# NOR.net
KiCad netlist of a schematic drawn in Altium Designer
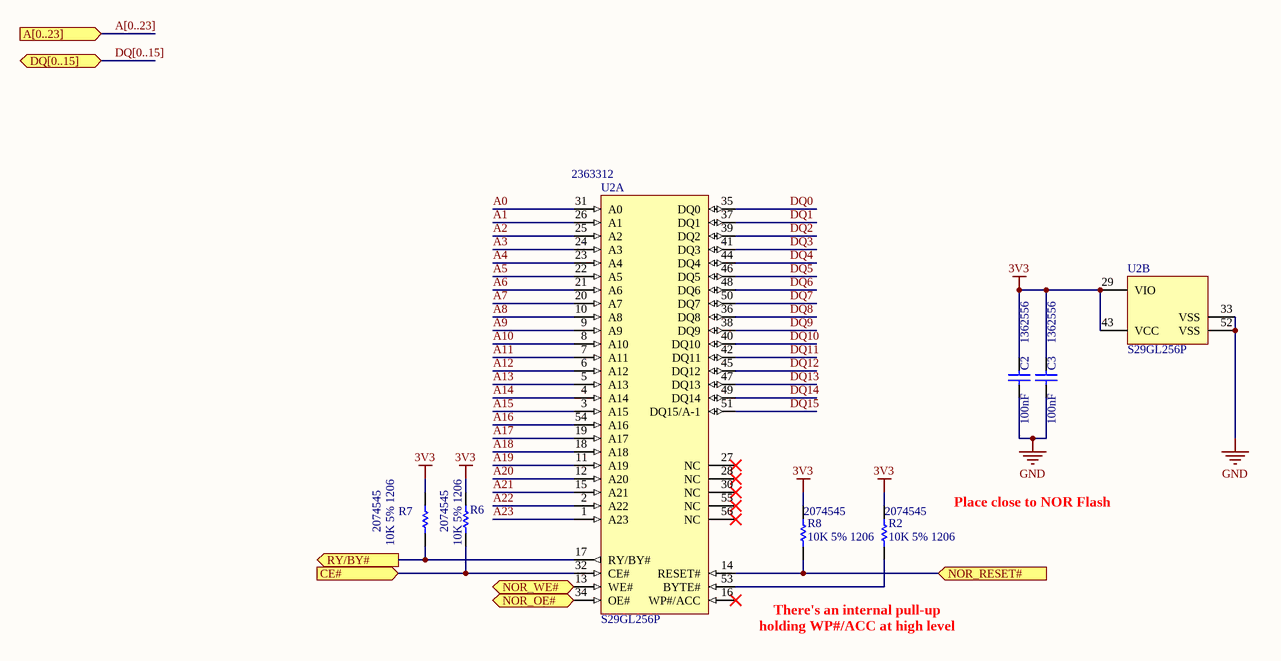
[diagram p0: NOR.SchDoc]

(export (version "E")
  (design (tool "Eeschema 10.0.6"))
  (components
    (comp (ref "C2")
      (value "100nF")
      (footprint "CAPC0603(1608)100_N")
      (description "CAP 100nF 50V ±10% 0603 (1608 Metric) Thickness 1mm SMD")
      (fields (field (name "TOLERANCE") "±10%") (field (name "SUPPLIER PART NUMBER 1") "1362556"))
      (libsource (lib "Altium Content Vault") (part "CMP-1035-02592-1"))
    )
    (comp (ref "C3")
      (value "100nF")
      (footprint "CAPC0603(1608)100_N")
      (description "CAP 100nF 50V ±10% 0603 (1608 Metric) Thickness 1mm SMD")
      (fields (field (name "TOLERANCE") "±10%") (field (name "SUPPLIER PART NUMBER 1") "1362556"))
      (libsource (lib "Altium Content Vault") (part "CMP-1035-02592-1"))
    )
    (comp (ref "R2")
      (value "10K 5% 1206")
      (footprint "RESC1206(3216)_M")
      (description "10K 0.25W 5% 1206 (3216 Metric)  SMD")
      (fields
        (field (name "POWER") "0.25 W")
        (field (name "TOLERANCE") "5 %")
        (field (name "SUPPLIER PART NUMBER 1") "2074545")
      )
      (libsource (lib "Altium Content Vault") (part "CMP-1014-00098-1"))
    )
    (comp (ref "R6")
      (value "10K 5% 1206")
      (footprint "RESC1206(3216)_M")
      (description "10K 0.25W 5% 1206 (3216 Metric)  SMD")
      (fields
        (field (name "POWER") "0.25 W")
        (field (name "TOLERANCE") "5 %")
        (field (name "SUPPLIER PART NUMBER 1") "2074545")
      )
      (libsource (lib "Altium Content Vault") (part "CMP-1014-00098-1"))
    )
    (comp (ref "R7")
      (value "10K 5% 1206")
      (footprint "RESC1206(3216)_M")
      (description "10K 0.25W 5% 1206 (3216 Metric)  SMD")
      (fields
        (field (name "POWER") "0.25 W")
        (field (name "TOLERANCE") "5 %")
        (field (name "SUPPLIER PART NUMBER 1") "2074545")
      )
      (libsource (lib "Altium Content Vault") (part "CMP-1014-00098-1"))
    )
    (comp (ref "R8")
      (value "10K 5% 1206")
      (footprint "RESC1206(3216)_M")
      (description "10K 0.25W 5% 1206 (3216 Metric)  SMD")
      (fields
        (field (name "POWER") "0.25 W")
        (field (name "TOLERANCE") "5 %")
        (field (name "SUPPLIER PART NUMBER 1") "2074545")
      )
      (libsource (lib "Altium Content Vault") (part "CMP-1014-00098-1"))
    )
    (comp (ref "U2")
      (value "S29GL256P")
      (footprint "56-Pin_Standard_TSOP")
      (fields (field (name "SUPPLIER PART NUMBER 1") "2363312"))
      (libsource (lib "S29GL256P90TFIR20") (part "S29GL256P"))
    )
  )
  (nets
    (net (code "1") (name "/A0") (class "Default")
      (node (ref "U2") (pin "31") (pinfunction "A0_31") (pintype "input"))
    )
    (net (code "2") (name "/A1") (class "Default")
      (node (ref "U2") (pin "26") (pinfunction "A1_26") (pintype "input"))
    )
    (net (code "3") (name "/A2") (class "Default")
      (node (ref "U2") (pin "25") (pinfunction "A2_25") (pintype "input"))
    )
    (net (code "4") (name "/A3") (class "Default")
      (node (ref "U2") (pin "24") (pinfunction "A3_24") (pintype "input"))
    )
    (net (code "5") (name "/A4") (class "Default")
      (node (ref "U2") (pin "23") (pinfunction "A4_23") (pintype "input"))
    )
    (net (code "6") (name "/A5") (class "Default")
      (node (ref "U2") (pin "22") (pinfunction "A5_22") (pintype "input"))
    )
    (net (code "7") (name "/A6") (class "Default")
      (node (ref "U2") (pin "21") (pinfunction "A6_21") (pintype "input"))
    )
    (net (code "8") (name "/A7") (class "Default")
      (node (ref "U2") (pin "20") (pinfunction "A7_20") (pintype "input"))
    )
    (net (code "9") (name "/A8") (class "Default")
      (node (ref "U2") (pin "10") (pinfunction "A8_10") (pintype "input"))
    )
    (net (code "10") (name "/A9") (class "Default")
      (node (ref "U2") (pin "9") (pinfunction "A9_9") (pintype "input"))
    )
    (net (code "11") (name "/A10") (class "Default")
      (node (ref "U2") (pin "8") (pinfunction "A10_8") (pintype "input"))
    )
    (net (code "12") (name "/A11") (class "Default")
      (node (ref "U2") (pin "7") (pinfunction "A11_7") (pintype "input"))
    )
    (net (code "13") (name "/A12") (class "Default")
      (node (ref "U2") (pin "6") (pinfunction "A12_6") (pintype "input"))
    )
    (net (code "14") (name "/A13") (class "Default")
      (node (ref "U2") (pin "5") (pinfunction "A13_5") (pintype "input"))
    )
    (net (code "15") (name "/A14") (class "Default")
      (node (ref "U2") (pin "4") (pinfunction "A14_4") (pintype "input"))
    )
    (net (code "16") (name "/A15") (class "Default")
      (node (ref "U2") (pin "3") (pinfunction "A15_3") (pintype "input"))
    )
    (net (code "17") (name "/A16") (class "Default")
      (node (ref "U2") (pin "54") (pinfunction "A16_54") (pintype "input"))
    )
    (net (code "18") (name "/A17") (class "Default")
      (node (ref "U2") (pin "19") (pinfunction "A17_19") (pintype "input"))
    )
    (net (code "19") (name "/A18") (class "Default")
      (node (ref "U2") (pin "18") (pinfunction "A18_18") (pintype "input"))
    )
    (net (code "20") (name "/A19") (class "Default")
      (node (ref "U2") (pin "11") (pinfunction "A19_11") (pintype "input"))
    )
    (net (code "21") (name "/A20") (class "Default")
      (node (ref "U2") (pin "12") (pinfunction "A20_12") (pintype "input"))
    )
    (net (code "22") (name "/A21") (class "Default")
      (node (ref "U2") (pin "15") (pinfunction "A21_15") (pintype "input"))
    )
    (net (code "23") (name "/A22") (class "Default")
      (node (ref "U2") (pin "2") (pinfunction "A22_2") (pintype "input"))
    )
    (net (code "24") (name "/A23") (class "Default")
      (node (ref "U2") (pin "1") (pinfunction "A23_1") (pintype "input"))
    )
    (net (code "26") (name "/CE#") (class "Default")
      (node (ref "R6") (pin "1") (pinfunction "1_1") (pintype "passive"))
      (node (ref "U2") (pin "32") (pinfunction "CE#_32") (pintype "input"))
    )
    (net (code "27") (name "/DQ0") (class "Default")
      (node (ref "U2") (pin "35") (pinfunction "DQ0_35") (pintype "bidirectional"))
    )
    (net (code "28") (name "/DQ1") (class "Default")
      (node (ref "U2") (pin "37") (pinfunction "DQ1_37") (pintype "bidirectional"))
    )
    (net (code "29") (name "/DQ2") (class "Default")
      (node (ref "U2") (pin "39") (pinfunction "DQ2_39") (pintype "bidirectional"))
    )
    (net (code "30") (name "/DQ3") (class "Default")
      (node (ref "U2") (pin "41") (pinfunction "DQ3_41") (pintype "bidirectional"))
    )
    (net (code "31") (name "/DQ4") (class "Default")
      (node (ref "U2") (pin "44") (pinfunction "DQ4_44") (pintype "bidirectional"))
    )
    (net (code "32") (name "/DQ5") (class "Default")
      (node (ref "U2") (pin "46") (pinfunction "DQ5_46") (pintype "bidirectional"))
    )
    (net (code "33") (name "/DQ6") (class "Default")
      (node (ref "U2") (pin "48") (pinfunction "DQ6_48") (pintype "bidirectional"))
    )
    (net (code "34") (name "/DQ7") (class "Default")
      (node (ref "U2") (pin "50") (pinfunction "DQ7_50") (pintype "bidirectional"))
    )
    (net (code "35") (name "/DQ8") (class "Default")
      (node (ref "U2") (pin "36") (pinfunction "DQ8_36") (pintype "bidirectional"))
    )
    (net (code "36") (name "/DQ9") (class "Default")
      (node (ref "U2") (pin "38") (pinfunction "DQ9_38") (pintype "bidirectional"))
    )
    (net (code "37") (name "/DQ10") (class "Default")
      (node (ref "U2") (pin "40") (pinfunction "DQ10_40") (pintype "bidirectional"))
    )
    (net (code "38") (name "/DQ11") (class "Default")
      (node (ref "U2") (pin "42") (pinfunction "DQ11_42") (pintype "bidirectional"))
    )
    (net (code "39") (name "/DQ12") (class "Default")
      (node (ref "U2") (pin "45") (pinfunction "DQ12_45") (pintype "bidirectional"))
    )
    (net (code "40") (name "/DQ13") (class "Default")
      (node (ref "U2") (pin "47") (pinfunction "DQ13_47") (pintype "bidirectional"))
    )
    (net (code "41") (name "/DQ14") (class "Default")
      (node (ref "U2") (pin "49") (pinfunction "DQ14_49") (pintype "bidirectional"))
    )
    (net (code "42") (name "/DQ15") (class "Default")
      (node (ref "U2") (pin "51") (pinfunction "DQ15/A-1_51") (pintype "bidirectional"))
    )
    (net (code "44") (name "/NOR_OE#") (class "Default")
      (node (ref "U2") (pin "34") (pinfunction "OE#_34") (pintype "input"))
    )
    (net (code "45") (name "/NOR_RESET#") (class "Default")
      (node (ref "R8") (pin "1") (pinfunction "1_1") (pintype "passive"))
      (node (ref "U2") (pin "14") (pinfunction "RESET#_14") (pintype "input"))
    )
    (net (code "46") (name "/NOR_WE#") (class "Default")
      (node (ref "U2") (pin "13") (pinfunction "WE#_13") (pintype "input"))
    )
    (net (code "47") (name "/RY{slash}BY#") (class "Default")
      (node (ref "R7") (pin "1") (pinfunction "1_1") (pintype "passive"))
      (node (ref "U2") (pin "17") (pinfunction "RY/BY#_17") (pintype "output"))
    )
    (net (code "48") (name "3V3") (class "Default")
      (node (ref "C2") (pin "2") (pinfunction "2_2") (pintype "passive"))
      (node (ref "C3") (pin "2") (pinfunction "2_2") (pintype "passive"))
      (node (ref "R2") (pin "2") (pinfunction "2_2") (pintype "passive"))
      (node (ref "R6") (pin "2") (pinfunction "2_2") (pintype "passive"))
      (node (ref "R7") (pin "2") (pinfunction "2_2") (pintype "passive"))
      (node (ref "R8") (pin "2") (pinfunction "2_2") (pintype "passive"))
      (node (ref "U2") (pin "29") (pinfunction "VIO_29") (pintype "power_in"))
      (node (ref "U2") (pin "43") (pinfunction "VCC_43") (pintype "power_in"))
    )
    (net (code "49") (name "GND") (class "Default")
      (node (ref "C2") (pin "1") (pinfunction "1_1") (pintype "passive"))
      (node (ref "C3") (pin "1") (pinfunction "1_1") (pintype "passive"))
      (node (ref "U2") (pin "33") (pinfunction "VSS_33") (pintype "power_in"))
      (node (ref "U2") (pin "52") (pinfunction "VSS_52") (pintype "power_in"))
    )
    (net (code "50") (name "Net-(U2A-BYTE#)") (class "Default")
      (node (ref "R2") (pin "1") (pinfunction "1_1") (pintype "passive"))
      (node (ref "U2") (pin "53") (pinfunction "BYTE#_53") (pintype "input"))
    )
    (net (code "51") (name "unconnected-(U2A-NC-Pad27)") (class "Default")
      (node (ref "U2") (pin "27") (pinfunction "NC_27") (pintype "passive+no_connect"))
    )
    (net (code "52") (name "unconnected-(U2A-NC-Pad28)") (class "Default")
      (node (ref "U2") (pin "28") (pinfunction "NC_28") (pintype "passive+no_connect"))
    )
    (net (code "53") (name "unconnected-(U2A-NC-Pad30)") (class "Default")
      (node (ref "U2") (pin "30") (pinfunction "NC_30") (pintype "passive+no_connect"))
    )
    (net (code "54") (name "unconnected-(U2A-NC-Pad55)") (class "Default")
      (node (ref "U2") (pin "55") (pinfunction "NC_55") (pintype "passive+no_connect"))
    )
    (net (code "55") (name "unconnected-(U2A-NC-Pad56)") (class "Default")
      (node (ref "U2") (pin "56") (pinfunction "NC_56") (pintype "passive+no_connect"))
    )
    (net (code "56") (name "unconnected-(U2A-WP#{slash}ACC-Pad16)") (class "Default")
      (node (ref "U2") (pin "16") (pinfunction "WP#/ACC_16") (pintype "input+no_connect"))
    )
  )
)
